# microcontroller.net
KiCad netlist of a schematic drawn in Altium Designer
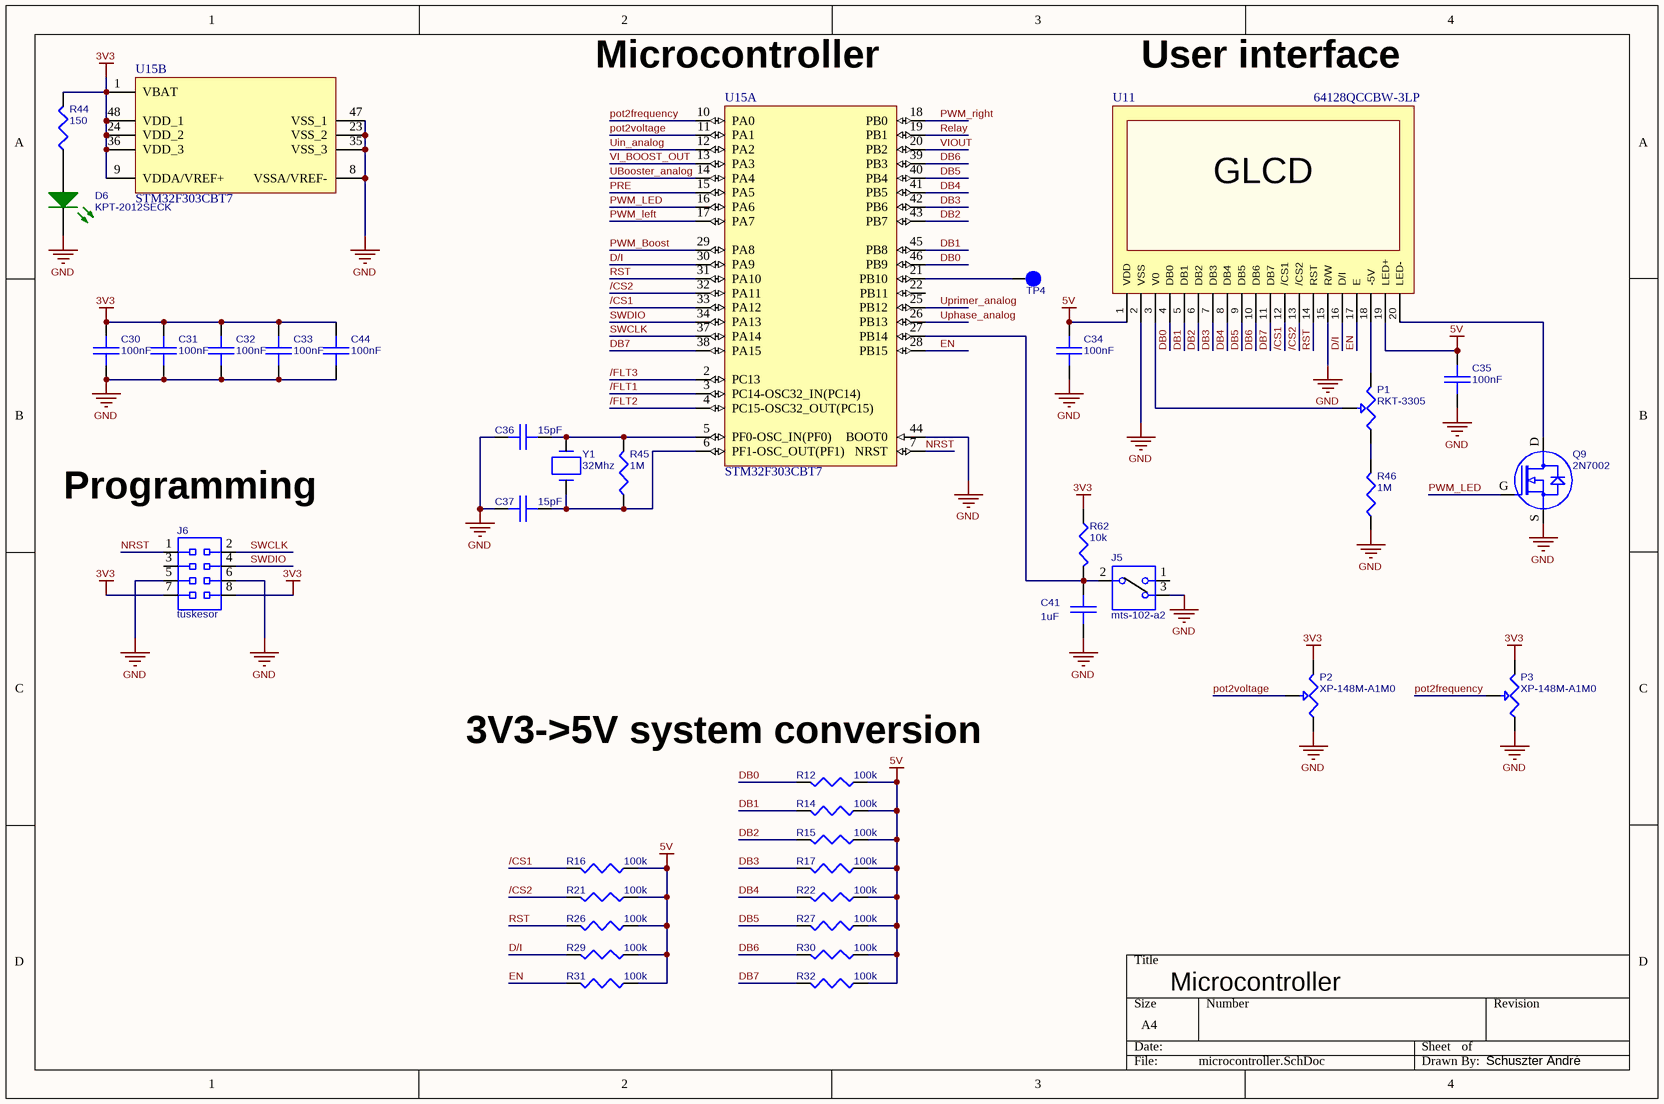
[diagram p0: microcontroller.SchDoc]

(export (version "E")
  (design (tool "Eeschema 10.0.6"))
  (components
    (comp (ref "C30")
      (value "100nF")
      (footprint "CAPC2012X06N")
      (description "82-07-32")
      (libsource (lib "PCB_PASSIVE") (part "CAPC"))
    )
    (comp (ref "C31")
      (value "100nF")
      (footprint "CAPC2012X06N")
      (description "82-07-32")
      (libsource (lib "PCB_PASSIVE") (part "CAPC"))
    )
    (comp (ref "C32")
      (value "100nF")
      (footprint "CAPC2012X06N")
      (description "82-07-32")
      (libsource (lib "PCB_PASSIVE") (part "CAPC"))
    )
    (comp (ref "C33")
      (value "100nF")
      (footprint "CAPC2012X06N")
      (description "82-07-32")
      (libsource (lib "PCB_PASSIVE") (part "CAPC"))
    )
    (comp (ref "C34")
      (value "100nF")
      (footprint "CAPC2012X06N")
      (description "82-07-32")
      (libsource (lib "PCB_PASSIVE") (part "CAPC"))
    )
    (comp (ref "C35")
      (value "100nF")
      (footprint "CAPC2012X06N")
      (description "82-07-32")
      (libsource (lib "PCB_PASSIVE") (part "CAPC"))
    )
    (comp (ref "C36")
      (value "15pF")
      (footprint "CAPC2012X06N")
      (description "82-00-94")
      (libsource (lib "PCB_PASSIVE") (part "CAPC"))
    )
    (comp (ref "C37")
      (value "15pF")
      (footprint "CAPC2012X06N")
      (description "82-00-94")
      (libsource (lib "PCB_PASSIVE") (part "CAPC"))
    )
    (comp (ref "C41")
      (value "1uF")
      (footprint "CAPC2012X06N")
      (description "2495497")
      (libsource (lib "PCB_PASSIVE") (part "CAPC"))
    )
    (comp (ref "C44")
      (value "100nF")
      (footprint "CAPC2012X06N")
      (description "82-07-32")
      (libsource (lib "PCB_PASSIVE") (part "CAPC"))
    )
    (comp (ref "D6")
      (value "KPT-2012SECK")
      (footprint "LED2012X11N_GREEN")
      (description "2099237")
      (libsource (lib "PCB_SMALL") (part "LED_GREEN"))
    )
    (comp (ref "J5")
      (value "mts-102-a2")
      (footprint "TOGGLE")
      (description "45-08-76")
      (fields
        (field (name "PART NUMBER") "TOGGLE D= 6 3P SPDT MTS-102-A2 (FEM) ON-ON 6A 125VAC 1AK.2ALL.PCB")
      )
      (libsource (lib "Schlib1") (part "TOGGLE_SPDT"))
    )
    (comp (ref "J6")
      (value "tüskesor")
      (footprint "PINH_M_2X4_100MIL_TH_HARWIN")
      (libsource (lib "PCB_CONNECTOR") (part "CON_2X4"))
    )
    (comp (ref "P1")
      (value "RKT-3305")
      (footprint "TRIMMER")
      (description "90-00-58")
      (libsource (lib "Schlib1") (part "TRIMMER"))
    )
    (comp (ref "P2")
      (value "XP-148M-A1M0")
      (footprint "potmeter")
      (description "06-03-80")
      (libsource (lib "Schlib1") (part "Potmeter"))
    )
    (comp (ref "P3")
      (value "XP-148M-A1M0")
      (footprint "potmeter")
      (description "06-03-80")
      (libsource (lib "Schlib1") (part "Potmeter"))
    )
    (comp (ref "Q9")
      (value "2N7002")
      (footprint "SOT95P240X111_SGD-3N")
      (description "86-00-97")
      (fields (field (name "PART NUMBER") "2N7002 (NXP) N-FET 60V 0.3A 0.83W Rds>5R SOT-23 ˝12W˝ (SN7002)"))
      (libsource (lib "Schlib1") (part "RELÉ_NFET"))
    )
    (comp (ref "R12")
      (value "100k")
      (footprint "RESC2012X06N")
      (description "81-11-11")
      (libsource (lib "PCB_PASSIVE") (part "RES_US_HOR"))
    )
    (comp (ref "R14")
      (value "100k")
      (footprint "RESC2012X06N")
      (description "81-11-11")
      (libsource (lib "PCB_PASSIVE") (part "RES_US_HOR"))
    )
    (comp (ref "R15")
      (value "100k")
      (footprint "RESC2012X06N")
      (description "81-11-11")
      (libsource (lib "PCB_PASSIVE") (part "RES_US_HOR"))
    )
    (comp (ref "R16")
      (value "100k")
      (footprint "RESC2012X06N")
      (description "81-11-11")
      (libsource (lib "PCB_PASSIVE") (part "RES_US_HOR"))
    )
    (comp (ref "R17")
      (value "100k")
      (footprint "RESC2012X06N")
      (description "81-11-11")
      (libsource (lib "PCB_PASSIVE") (part "RES_US_HOR"))
    )
    (comp (ref "R21")
      (value "100k")
      (footprint "RESC2012X06N")
      (description "81-11-11")
      (libsource (lib "PCB_PASSIVE") (part "RES_US_HOR"))
    )
    (comp (ref "R22")
      (value "100k")
      (footprint "RESC2012X06N")
      (description "81-11-11")
      (libsource (lib "PCB_PASSIVE") (part "RES_US_HOR"))
    )
    (comp (ref "R26")
      (value "100k")
      (footprint "RESC2012X06N")
      (description "81-11-11")
      (libsource (lib "PCB_PASSIVE") (part "RES_US_HOR"))
    )
    (comp (ref "R27")
      (value "100k")
      (footprint "RESC2012X06N")
      (description "81-11-11")
      (libsource (lib "PCB_PASSIVE") (part "RES_US_HOR"))
    )
    (comp (ref "R29")
      (value "100k")
      (footprint "RESC2012X06N")
      (description "81-11-11")
      (libsource (lib "PCB_PASSIVE") (part "RES_US_HOR"))
    )
    (comp (ref "R30")
      (value "100k")
      (footprint "RESC2012X06N")
      (description "81-11-11")
      (libsource (lib "PCB_PASSIVE") (part "RES_US_HOR"))
    )
    (comp (ref "R31")
      (value "100k")
      (footprint "RESC2012X06N")
      (description "81-11-11")
      (libsource (lib "PCB_PASSIVE") (part "RES_US_HOR"))
    )
    (comp (ref "R32")
      (value "100k")
      (footprint "RESC2012X06N")
      (description "81-11-11")
      (libsource (lib "PCB_PASSIVE") (part "RES_US_HOR"))
    )
    (comp (ref "R44")
      (value "150")
      (footprint "RESC2012X06N")
      (description "81-10-77")
      (libsource (lib "PCB_PASSIVE") (part "RES_US_HOR"))
    )
    (comp (ref "R45")
      (value "1M")
      (footprint "RESC2012X06N")
      (description "81-11-22")
      (libsource (lib "PCB_PASSIVE") (part "RES_US_HOR"))
    )
    (comp (ref "R46")
      (value "1M")
      (footprint "RESC2012X06N")
      (description "81-11-22")
      (libsource (lib "PCB_PASSIVE") (part "RES_US_HOR"))
    )
    (comp (ref "R62")
      (value "10k")
      (footprint "RESC2012X06N")
      (description "80-10-98")
      (libsource (lib "PCB_PASSIVE") (part "RES_US_HOR"))
    )
    (comp (ref "TP4")
      (value "Comment")
      (footprint "TP200X150")
      (libsource (lib "PCB_VIRTUAL") (part "TP_SMD"))
    )
    (comp (ref "U11") (value "64128QCCBW-3LP") (footprint "LCD") (libsource (lib "Schlib1") (part "LCD")))
    (comp (ref "U15")
      (value "STM32F303CBT7")
      (footprint "STM-LQFP48_N")
      (libsource (lib "STMicroelectronics STM32 F3") (part "STM32F303CBT7"))
    )
    (comp (ref "Y1")
      (value "32Mhz")
      (footprint "XTAL")
      (description "40-01-35")
      (fields (field (name "PART NUMBER") "QUARZ HC49/S (NSK) 30ppm 20pF LOW PROFILE "))
      (libsource (lib "Schlib1") (part "XTAL"))
    )
  )
  (nets
    (net (code "1") (name "/DB0") (class "Default")
      (node (ref "R12") (pin "2") (pinfunction "2_2") (pintype "passive"))
      (node (ref "U11") (pin "4") (pinfunction "DB0_4") (pintype "passive"))
      (node (ref "U15") (pin "46") (pinfunction "PB9_46") (pintype "bidirectional"))
    )
    (net (code "2") (name "/DB1") (class "Default")
      (node (ref "R14") (pin "2") (pinfunction "2_2") (pintype "passive"))
      (node (ref "U11") (pin "5") (pinfunction "DB1_5") (pintype "passive"))
      (node (ref "U15") (pin "45") (pinfunction "PB8_45") (pintype "bidirectional"))
    )
    (net (code "3") (name "/DB2") (class "Default")
      (node (ref "R15") (pin "2") (pinfunction "2_2") (pintype "passive"))
      (node (ref "U11") (pin "6") (pinfunction "DB2_6") (pintype "passive"))
      (node (ref "U15") (pin "43") (pinfunction "PB7_43") (pintype "bidirectional"))
    )
    (net (code "4") (name "/DB3") (class "Default")
      (node (ref "R17") (pin "2") (pinfunction "2_2") (pintype "passive"))
      (node (ref "U11") (pin "7") (pinfunction "DB3_7") (pintype "passive"))
      (node (ref "U15") (pin "42") (pinfunction "PB6_42") (pintype "bidirectional"))
    )
    (net (code "5") (name "/DB4") (class "Default")
      (node (ref "R22") (pin "2") (pinfunction "2_2") (pintype "passive"))
      (node (ref "U11") (pin "8") (pinfunction "DB4_8") (pintype "passive"))
      (node (ref "U15") (pin "41") (pinfunction "PB5_41") (pintype "bidirectional"))
    )
    (net (code "6") (name "/DB5") (class "Default")
      (node (ref "R27") (pin "2") (pinfunction "2_2") (pintype "passive"))
      (node (ref "U11") (pin "9") (pinfunction "DB5_9") (pintype "passive"))
      (node (ref "U15") (pin "40") (pinfunction "PB4_40") (pintype "bidirectional"))
    )
    (net (code "7") (name "/DB6") (class "Default")
      (node (ref "R30") (pin "2") (pinfunction "2_2") (pintype "passive"))
      (node (ref "U11") (pin "10") (pinfunction "DB6_10") (pintype "passive"))
      (node (ref "U15") (pin "39") (pinfunction "PB3_39") (pintype "bidirectional"))
    )
    (net (code "8") (name "/DB7") (class "Default")
      (node (ref "R32") (pin "2") (pinfunction "2_2") (pintype "passive"))
      (node (ref "U11") (pin "11") (pinfunction "DB7_11") (pintype "passive"))
      (node (ref "U15") (pin "38") (pinfunction "PA15_38") (pintype "bidirectional"))
    )
    (net (code "9") (name "/D{slash}I") (class "Default")
      (node (ref "R29") (pin "2") (pinfunction "2_2") (pintype "passive"))
      (node (ref "U11") (pin "16") (pinfunction "D/I_16") (pintype "passive"))
      (node (ref "U15") (pin "30") (pinfunction "PA9_30") (pintype "bidirectional"))
    )
    (net (code "10") (name "/EN") (class "Default")
      (node (ref "R31") (pin "2") (pinfunction "2_2") (pintype "passive"))
      (node (ref "U11") (pin "17") (pinfunction "E_17") (pintype "passive"))
      (node (ref "U15") (pin "28") (pinfunction "PB15_28") (pintype "bidirectional"))
    )
    (net (code "11") (name "/NRST") (class "Default")
      (node (ref "J6") (pin "1") (pinfunction "1_1") (pintype "passive"))
      (node (ref "U15") (pin "7") (pinfunction "NRST_7") (pintype "bidirectional"))
    )
    (net (code "12") (name "/PRE") (class "Default")
      (node (ref "U15") (pin "15") (pinfunction "PA5_15") (pintype "bidirectional"))
    )
    (net (code "13") (name "/PWM_Boost") (class "Default")
      (node (ref "U15") (pin "29") (pinfunction "PA8_29") (pintype "bidirectional"))
    )
    (net (code "14") (name "/PWM_LED") (class "Default")
      (node (ref "Q9") (pin "G") (pinfunction "G_G") (pintype "passive"))
      (node (ref "U15") (pin "16") (pinfunction "PA6_16") (pintype "bidirectional"))
    )
    (net (code "15") (name "/PWM_left") (class "Default")
      (node (ref "U15") (pin "17") (pinfunction "PA7_17") (pintype "bidirectional"))
    )
    (net (code "16") (name "/PWM_right") (class "Default")
      (node (ref "U15") (pin "18") (pinfunction "PB0_18") (pintype "bidirectional"))
    )
    (net (code "17") (name "/RST") (class "Default")
      (node (ref "R26") (pin "2") (pinfunction "2_2") (pintype "passive"))
      (node (ref "U11") (pin "14") (pinfunction "RST_14") (pintype "passive"))
      (node (ref "U15") (pin "31") (pinfunction "PA10_31") (pintype "bidirectional"))
    )
    (net (code "18") (name "/Relay") (class "Default")
      (node (ref "U15") (pin "19") (pinfunction "PB1_19") (pintype "bidirectional"))
    )
    (net (code "19") (name "/SWCLK") (class "Default")
      (node (ref "J6") (pin "2") (pinfunction "2_2") (pintype "passive"))
      (node (ref "U15") (pin "37") (pinfunction "PA14_37") (pintype "bidirectional"))
    )
    (net (code "20") (name "/SWDIO") (class "Default")
      (node (ref "J6") (pin "4") (pinfunction "4_4") (pintype "passive"))
      (node (ref "U15") (pin "34") (pinfunction "PA13_34") (pintype "bidirectional"))
    )
    (net (code "21") (name "/UBooster_analog") (class "Default")
      (node (ref "U15") (pin "14") (pinfunction "PA4_14") (pintype "bidirectional"))
    )
    (net (code "22") (name "/Uin_analog") (class "Default")
      (node (ref "U15") (pin "12") (pinfunction "PA2_12") (pintype "bidirectional"))
    )
    (net (code "23") (name "/Uphase_analog") (class "Default")
      (node (ref "U15") (pin "26") (pinfunction "PB13_26") (pintype "bidirectional"))
    )
    (net (code "24") (name "/Uprimer_analog") (class "Default")
      (node (ref "U15") (pin "25") (pinfunction "PB12_25") (pintype "bidirectional"))
    )
    (net (code "25") (name "/VIOUT") (class "Default")
      (node (ref "U15") (pin "20") (pinfunction "PB2_20") (pintype "bidirectional"))
    )
    (net (code "26") (name "/VI_BOOST_OUT") (class "Default")
      (node (ref "U15") (pin "13") (pinfunction "PA3_13") (pintype "bidirectional"))
    )
    (net (code "27") (name "/pot2frequency") (class "Default")
      (node (ref "P3") (pin "2") (pinfunction "2_2") (pintype "passive"))
      (node (ref "U15") (pin "10") (pinfunction "PA0_10") (pintype "bidirectional"))
    )
    (net (code "28") (name "/pot2voltage") (class "Default")
      (node (ref "P2") (pin "2") (pinfunction "2_2") (pintype "passive"))
      (node (ref "U15") (pin "11") (pinfunction "PA1_11") (pintype "bidirectional"))
    )
    (net (code "29") (name "/{slash}CS1") (class "Default")
      (node (ref "R16") (pin "2") (pinfunction "2_2") (pintype "passive"))
      (node (ref "U11") (pin "12") (pinfunction "/CS1_12") (pintype "passive"))
      (node (ref "U15") (pin "33") (pinfunction "PA12_33") (pintype "bidirectional"))
    )
    (net (code "30") (name "/{slash}CS2") (class "Default")
      (node (ref "R21") (pin "2") (pinfunction "2_2") (pintype "passive"))
      (node (ref "U11") (pin "13") (pinfunction "/CS2_13") (pintype "passive"))
      (node (ref "U15") (pin "32") (pinfunction "PA11_32") (pintype "bidirectional"))
    )
    (net (code "31") (name "/{slash}FLT1") (class "Default")
      (node (ref "U15") (pin "3") (pinfunction "PC14-OSC32_IN(PC14)_3") (pintype "bidirectional"))
    )
    (net (code "32") (name "/{slash}FLT2") (class "Default")
      (node (ref "U15") (pin "4") (pinfunction "PC15-OSC32_OUT(PC15)_4") (pintype "bidirectional"))
    )
    (net (code "33") (name "/{slash}FLT3") (class "Default")
      (node (ref "U15") (pin "2") (pinfunction "PC13_2") (pintype "bidirectional"))
    )
    (net (code "34") (name "3V3") (class "Default")
      (node (ref "C30") (pin "1") (pinfunction "1_1") (pintype "passive"))
      (node (ref "C31") (pin "1") (pinfunction "1_1") (pintype "passive"))
      (node (ref "C32") (pin "1") (pinfunction "1_1") (pintype "passive"))
      (node (ref "C33") (pin "1") (pinfunction "1_1") (pintype "passive"))
      (node (ref "C44") (pin "1") (pinfunction "1_1") (pintype "passive"))
      (node (ref "J6") (pin "7") (pinfunction "7_7") (pintype "passive"))
      (node (ref "J6") (pin "8") (pinfunction "8_8") (pintype "passive"))
      (node (ref "P2") (pin "3") (pinfunction "3_3") (pintype "passive"))
      (node (ref "P3") (pin "3") (pinfunction "3_3") (pintype "passive"))
      (node (ref "R44") (pin "2") (pinfunction "2_2") (pintype "passive"))
      (node (ref "R62") (pin "2") (pinfunction "2_2") (pintype "passive"))
      (node (ref "U15") (pin "1") (pinfunction "VBAT_1") (pintype "power_in"))
      (node (ref "U15") (pin "24") (pinfunction "VDD_2_24") (pintype "power_in"))
      (node (ref "U15") (pin "36") (pinfunction "VDD_3_36") (pintype "power_in"))
      (node (ref "U15") (pin "48") (pinfunction "VDD_1_48") (pintype "power_in"))
      (node (ref "U15") (pin "9") (pinfunction "VDDA/VREF+_9") (pintype "power_in"))
    )
    (net (code "35") (name "5V") (class "Default")
      (node (ref "C34") (pin "1") (pinfunction "1_1") (pintype "passive"))
      (node (ref "C35") (pin "1") (pinfunction "1_1") (pintype "passive"))
      (node (ref "R12") (pin "1") (pinfunction "1_1") (pintype "passive"))
      (node (ref "R14") (pin "1") (pinfunction "1_1") (pintype "passive"))
      (node (ref "R15") (pin "1") (pinfunction "1_1") (pintype "passive"))
      (node (ref "R16") (pin "1") (pinfunction "1_1") (pintype "passive"))
      (node (ref "R17") (pin "1") (pinfunction "1_1") (pintype "passive"))
      (node (ref "R21") (pin "1") (pinfunction "1_1") (pintype "passive"))
      (node (ref "R22") (pin "1") (pinfunction "1_1") (pintype "passive"))
      (node (ref "R26") (pin "1") (pinfunction "1_1") (pintype "passive"))
      (node (ref "R27") (pin "1") (pinfunction "1_1") (pintype "passive"))
      (node (ref "R29") (pin "1") (pinfunction "1_1") (pintype "passive"))
      (node (ref "R30") (pin "1") (pinfunction "1_1") (pintype "passive"))
      (node (ref "R31") (pin "1") (pinfunction "1_1") (pintype "passive"))
      (node (ref "R32") (pin "1") (pinfunction "1_1") (pintype "passive"))
      (node (ref "U11") (pin "1") (pinfunction "VDD_1") (pintype "passive"))
      (node (ref "U11") (pin "19") (pinfunction "LED+_19") (pintype "passive"))
    )
    (net (code "36") (name "GND") (class "Default")
      (node (ref "C30") (pin "2") (pinfunction "2_2") (pintype "passive"))
      (node (ref "C31") (pin "2") (pinfunction "2_2") (pintype "passive"))
      (node (ref "C32") (pin "2") (pinfunction "2_2") (pintype "passive"))
      (node (ref "C33") (pin "2") (pinfunction "2_2") (pintype "passive"))
      (node (ref "C34") (pin "2") (pinfunction "2_2") (pintype "passive"))
      (node (ref "C35") (pin "2") (pinfunction "2_2") (pintype "passive"))
      (node (ref "C36") (pin "1") (pinfunction "1_1") (pintype "passive"))
      (node (ref "C37") (pin "1") (pinfunction "1_1") (pintype "passive"))
      (node (ref "C41") (pin "2") (pinfunction "2_2") (pintype "passive"))
      (node (ref "C44") (pin "2") (pinfunction "2_2") (pintype "passive"))
      (node (ref "D6") (pin "C") (pinfunction "C_C") (pintype "passive"))
      (node (ref "J5") (pin "3") (pinfunction "3_3") (pintype "passive"))
      (node (ref "J6") (pin "5") (pinfunction "5_5") (pintype "passive"))
      (node (ref "J6") (pin "6") (pinfunction "6_6") (pintype "passive"))
      (node (ref "P2") (pin "1") (pinfunction "1_1") (pintype "passive"))
      (node (ref "P3") (pin "1") (pinfunction "1_1") (pintype "passive"))
      (node (ref "Q9") (pin "S") (pinfunction "S_S") (pintype "passive"))
      (node (ref "R46") (pin "1") (pinfunction "1_1") (pintype "passive"))
      (node (ref "U11") (pin "15") (pinfunction "R/W_15") (pintype "passive"))
      (node (ref "U11") (pin "2") (pinfunction "VSS_2") (pintype "passive"))
      (node (ref "U15") (pin "23") (pinfunction "VSS_2_23") (pintype "power_in"))
      (node (ref "U15") (pin "35") (pinfunction "VSS_3_35") (pintype "power_in"))
      (node (ref "U15") (pin "44") (pinfunction "BOOT0_44") (pintype "input"))
      (node (ref "U15") (pin "47") (pinfunction "VSS_1_47") (pintype "power_in"))
      (node (ref "U15") (pin "8") (pinfunction "VSSA/VREF-_8") (pintype "power_in"))
    )
    (net (code "37") (name "Net-(D6-PadA)") (class "Default")
      (node (ref "D6") (pin "A") (pinfunction "A_A") (pintype "passive"))
      (node (ref "R44") (pin "1") (pinfunction "1_1") (pintype "passive"))
    )
    (net (code "38") (name "Net-(P1-Pad1)") (class "Default")
      (node (ref "P1") (pin "1") (pinfunction "1_1") (pintype "passive"))
      (node (ref "R46") (pin "2") (pinfunction "2_2") (pintype "passive"))
    )
    (net (code "39") (name "Net-(TP4-Pin1)") (class "Default")
      (node (ref "TP4") (pin "1") (pinfunction "Pin1_1") (pintype "passive"))
      (node (ref "U15") (pin "21") (pinfunction "PB10_21") (pintype "bidirectional"))
    )
    (net (code "40") (name "Net-(U11--5V)") (class "Default")
      (node (ref "P1") (pin "3") (pinfunction "3_3") (pintype "passive"))
      (node (ref "U11") (pin "18") (pinfunction "-5V_18") (pintype "passive"))
    )
    (net (code "41") (name "Net-(U11-LED-)") (class "Default")
      (node (ref "Q9") (pin "D") (pinfunction "D_D") (pintype "passive"))
      (node (ref "U11") (pin "20") (pinfunction "LED-_20") (pintype "passive"))
    )
    (net (code "42") (name "Net-(U11-V0)") (class "Default")
      (node (ref "P1") (pin "2") (pinfunction "2_2") (pintype "passive"))
      (node (ref "U11") (pin "3") (pinfunction "V0_3") (pintype "passive"))
    )
    (net (code "43") (name "Net-(U15A-PB14)") (class "Default")
      (node (ref "C41") (pin "1") (pinfunction "1_1") (pintype "passive"))
      (node (ref "J5") (pin "2") (pinfunction "2_2") (pintype "passive"))
      (node (ref "R62") (pin "1") (pinfunction "1_1") (pintype "passive"))
      (node (ref "U15") (pin "27") (pinfunction "PB14_27") (pintype "bidirectional"))
    )
    (net (code "44") (name "Net-(U15A-PF0-OSC_IN(PF0))") (class "Default")
      (node (ref "C36") (pin "2") (pinfunction "2_2") (pintype "passive"))
      (node (ref "R45") (pin "2") (pinfunction "2_2") (pintype "passive"))
      (node (ref "U15") (pin "5") (pinfunction "PF0-OSC_IN(PF0)_5") (pintype "bidirectional"))
      (node (ref "Y1") (pin "2") (pinfunction "2_2") (pintype "passive"))
    )
    (net (code "45") (name "Net-(U15A-PF1-OSC_OUT(PF1))") (class "Default")
      (node (ref "C37") (pin "2") (pinfunction "2_2") (pintype "passive"))
      (node (ref "R45") (pin "1") (pinfunction "1_1") (pintype "passive"))
      (node (ref "U15") (pin "6") (pinfunction "PF1-OSC_OUT(PF1)_6") (pintype "bidirectional"))
      (node (ref "Y1") (pin "1") (pinfunction "1_1") (pintype "passive"))
    )
    (net (code "46") (name "unconnected-(J5-Pad1)") (class "Default")
      (node (ref "J5") (pin "1") (pinfunction "1_1") (pintype "passive"))
    )
    (net (code "47") (name "unconnected-(J6-Pad3)") (class "Default")
      (node (ref "J6") (pin "3") (pinfunction "3_3") (pintype "passive"))
    )
    (net (code "48") (name "unconnected-(U15A-PB11-Pad22)") (class "Default")
      (node (ref "U15") (pin "22") (pinfunction "PB11_22") (pintype "bidirectional"))
    )
  )
)
